# Zotino_BNC_Adapter.net
KiCad netlist of a schematic drawn in Altium Designer
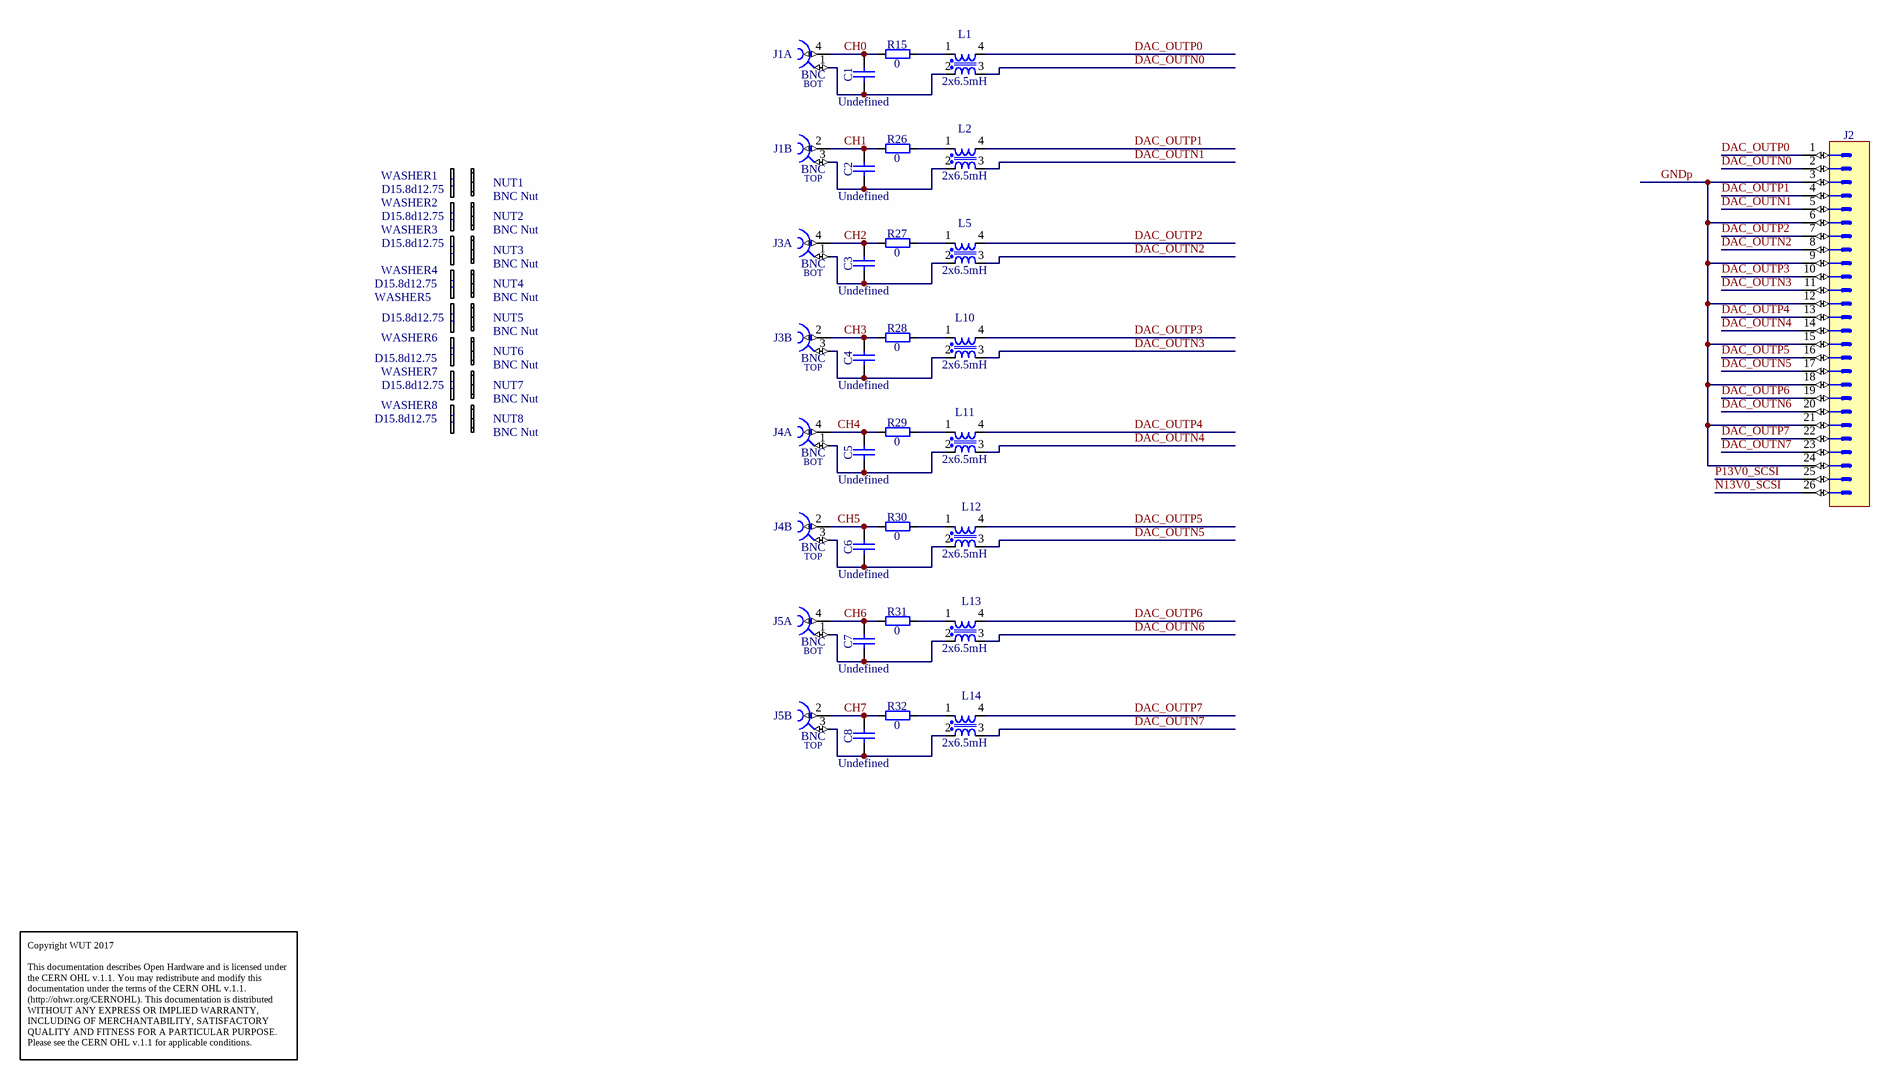
[diagram p0: Zotino_BNC_Adapter.SchDoc]

(export (version "E")
  (design (tool "Eeschema 10.0.6"))
  (components
    (comp (ref "C1")
      (value "Undefined")
      (footprint "CAPC2012X135N")
      (description "Non-polarised capacitor")
      (fields (field (name "PART NUMBER") "CC0805_NO-VALUE") (field (name "AUTHOR") "CERN DEM JLC"))
      (libsource (lib "Capacitors") (part "Capacitor - non polarized"))
    )
    (comp (ref "C2")
      (value "Undefined")
      (footprint "CAPC2012X135N")
      (description "Non-polarised capacitor")
      (fields (field (name "PART NUMBER") "CC0805_NO-VALUE") (field (name "AUTHOR") "CERN DEM JLC"))
      (libsource (lib "Capacitors") (part "Capacitor - non polarized"))
    )
    (comp (ref "C3")
      (value "Undefined")
      (footprint "CAPC2012X135N")
      (description "Non-polarised capacitor")
      (fields (field (name "PART NUMBER") "CC0805_NO-VALUE") (field (name "AUTHOR") "CERN DEM JLC"))
      (libsource (lib "Capacitors") (part "Capacitor - non polarized"))
    )
    (comp (ref "C4")
      (value "Undefined")
      (footprint "CAPC2012X135N")
      (description "Non-polarised capacitor")
      (fields (field (name "PART NUMBER") "CC0805_NO-VALUE") (field (name "AUTHOR") "CERN DEM JLC"))
      (libsource (lib "Capacitors") (part "Capacitor - non polarized"))
    )
    (comp (ref "C5")
      (value "Undefined")
      (footprint "CAPC2012X135N")
      (description "Non-polarised capacitor")
      (fields (field (name "PART NUMBER") "CC0805_NO-VALUE") (field (name "AUTHOR") "CERN DEM JLC"))
      (libsource (lib "Capacitors") (part "Capacitor - non polarized"))
    )
    (comp (ref "C6")
      (value "Undefined")
      (footprint "CAPC2012X135N")
      (description "Non-polarised capacitor")
      (fields (field (name "PART NUMBER") "CC0805_NO-VALUE") (field (name "AUTHOR") "CERN DEM JLC"))
      (libsource (lib "Capacitors") (part "Capacitor - non polarized"))
    )
    (comp (ref "C7")
      (value "Undefined")
      (footprint "CAPC2012X135N")
      (description "Non-polarised capacitor")
      (fields (field (name "PART NUMBER") "CC0805_NO-VALUE") (field (name "AUTHOR") "CERN DEM JLC"))
      (libsource (lib "Capacitors") (part "Capacitor - non polarized"))
    )
    (comp (ref "C8")
      (value "Undefined")
      (footprint "CAPC2012X135N")
      (description "Non-polarised capacitor")
      (fields (field (name "PART NUMBER") "CC0805_NO-VALUE") (field (name "AUTHOR") "CERN DEM JLC"))
      (libsource (lib "Capacitors") (part "Capacitor - non polarized"))
    )
    (comp (ref "J1")
      (value "BNC")
      (footprint "RENHOTEC_RHT-610-0049")
      (description "Dual Right Angle 50 Ohm BNC Jack, White Valox Case")
      (fields
        (field (name "PART NUMBER") "RENHOTEC_RHT-610-0049")
        (field (name "MANUFACTURER") "RENHOTEC")
        (field (name "AUTHOR") "GK")
      )
      (libsource (lib "LIBRARY_SCH") (part "CON_BNC_DUAL"))
    )
    (comp (ref "J2")
      (value "Header 26")
      (footprint "3M_N2526-6003RB")
      (description "Connector 26 Male")
      (fields
        (field (name "PART NUMBER") "3M_N2526-6003RB")
        (field (name "MANUFACTURER") "3M")
        (field (name "AUTHOR") "CERN DEM JLC")
      )
      (libsource (lib "Connectors") (part "Connector 26 Male"))
    )
    (comp (ref "J3")
      (value "BNC")
      (footprint "RENHOTEC_RHT-610-0049")
      (description "Dual Right Angle 50 Ohm BNC Jack, White Valox Case")
      (fields
        (field (name "PART NUMBER") "RENHOTEC_RHT-610-0049")
        (field (name "MANUFACTURER") "RENHOTEC")
        (field (name "AUTHOR") "GK")
      )
      (libsource (lib "LIBRARY_SCH") (part "CON_BNC_DUAL"))
    )
    (comp (ref "J4")
      (value "BNC")
      (footprint "RENHOTEC_RHT-610-0049")
      (description "Dual Right Angle 50 Ohm BNC Jack, White Valox Case")
      (fields
        (field (name "PART NUMBER") "RENHOTEC_RHT-610-0049")
        (field (name "MANUFACTURER") "RENHOTEC")
        (field (name "AUTHOR") "GK")
      )
      (libsource (lib "LIBRARY_SCH") (part "CON_BNC_DUAL"))
    )
    (comp (ref "J5")
      (value "BNC")
      (footprint "RENHOTEC_RHT-610-0049")
      (description "Dual Right Angle 50 Ohm BNC Jack, White Valox Case")
      (fields
        (field (name "PART NUMBER") "RENHOTEC_RHT-610-0049")
        (field (name "MANUFACTURER") "RENHOTEC")
        (field (name "AUTHOR") "GK")
      )
      (libsource (lib "LIBRARY_SCH") (part "CON_BNC_DUAL"))
    )
    (comp (ref "L1")
      (value "2x6.5mH")
      (footprint "IND_WURTH_WE-SL2")
      (description "Inductor Common Mode")
      (fields
        (field (name "PART NUMBER") "IND_6.5MH_50%_WURTH_WE-SL2-744229")
        (field (name "POWER") "400mA")
        (field (name "AUTHOR") "CERN DEM JLC")
      )
      (libsource (lib "Inductors & Transformers") (part "Inductor Common Mode 1Dot-4 2Dot-3"))
    )
    (comp (ref "L2")
      (value "2x6.5mH")
      (footprint "IND_WURTH_WE-SL2")
      (description "Inductor Common Mode")
      (fields
        (field (name "PART NUMBER") "IND_6.5MH_50%_WURTH_WE-SL2-744229")
        (field (name "POWER") "400mA")
        (field (name "AUTHOR") "CERN DEM JLC")
      )
      (libsource (lib "Inductors & Transformers") (part "Inductor Common Mode 1Dot-4 2Dot-3"))
    )
    (comp (ref "L5")
      (value "2x6.5mH")
      (footprint "IND_WURTH_WE-SL2")
      (description "Inductor Common Mode")
      (fields
        (field (name "PART NUMBER") "IND_6.5MH_50%_WURTH_WE-SL2-744229")
        (field (name "POWER") "400mA")
        (field (name "AUTHOR") "CERN DEM JLC")
      )
      (libsource (lib "Inductors & Transformers") (part "Inductor Common Mode 1Dot-4 2Dot-3"))
    )
    (comp (ref "L10")
      (value "2x6.5mH")
      (footprint "IND_WURTH_WE-SL2")
      (description "Inductor Common Mode")
      (fields
        (field (name "PART NUMBER") "IND_6.5MH_50%_WURTH_WE-SL2-744229")
        (field (name "POWER") "400mA")
        (field (name "AUTHOR") "CERN DEM JLC")
      )
      (libsource (lib "Inductors & Transformers") (part "Inductor Common Mode 1Dot-4 2Dot-3"))
    )
    (comp (ref "L11")
      (value "2x6.5mH")
      (footprint "IND_WURTH_WE-SL2")
      (description "Inductor Common Mode")
      (fields
        (field (name "PART NUMBER") "IND_6.5MH_50%_WURTH_WE-SL2-744229")
        (field (name "POWER") "400mA")
        (field (name "AUTHOR") "CERN DEM JLC")
      )
      (libsource (lib "Inductors & Transformers") (part "Inductor Common Mode 1Dot-4 2Dot-3"))
    )
    (comp (ref "L12")
      (value "2x6.5mH")
      (footprint "IND_WURTH_WE-SL2")
      (description "Inductor Common Mode")
      (fields
        (field (name "PART NUMBER") "IND_6.5MH_50%_WURTH_WE-SL2-744229")
        (field (name "POWER") "400mA")
        (field (name "AUTHOR") "CERN DEM JLC")
      )
      (libsource (lib "Inductors & Transformers") (part "Inductor Common Mode 1Dot-4 2Dot-3"))
    )
    (comp (ref "L13")
      (value "2x6.5mH")
      (footprint "IND_WURTH_WE-SL2")
      (description "Inductor Common Mode")
      (fields
        (field (name "PART NUMBER") "IND_6.5MH_50%_WURTH_WE-SL2-744229")
        (field (name "POWER") "400mA")
        (field (name "AUTHOR") "CERN DEM JLC")
      )
      (libsource (lib "Inductors & Transformers") (part "Inductor Common Mode 1Dot-4 2Dot-3"))
    )
    (comp (ref "L14")
      (value "2x6.5mH")
      (footprint "IND_WURTH_WE-SL2")
      (description "Inductor Common Mode")
      (fields
        (field (name "PART NUMBER") "IND_6.5MH_50%_WURTH_WE-SL2-744229")
        (field (name "POWER") "400mA")
        (field (name "AUTHOR") "CERN DEM JLC")
      )
      (libsource (lib "Inductors & Transformers") (part "Inductor Common Mode 1Dot-4 2Dot-3"))
    )
    (comp (ref "NUT1")
      (value "BNC Nut")
      (footprint "TE_1-329631-2")
      (description "BNC nut")
      (fields
        (field (name "PART NUMBER") "TE_1-329631-2")
        (field (name "MANUFACTURER") "TE")
        (field (name "AUTHOR") "CERN DEM JLC")
      )
      (libsource (lib "LIBRARY_SCH") (part "MECH_BNC_NUT"))
    )
    (comp (ref "NUT2")
      (value "BNC Nut")
      (footprint "TE_1-329631-2")
      (description "BNC nut")
      (fields
        (field (name "PART NUMBER") "TE_1-329631-2")
        (field (name "MANUFACTURER") "TE")
        (field (name "AUTHOR") "CERN DEM JLC")
      )
      (libsource (lib "LIBRARY_SCH") (part "MECH_BNC_NUT"))
    )
    (comp (ref "NUT3")
      (value "BNC Nut")
      (footprint "TE_1-329631-2")
      (description "BNC nut")
      (fields
        (field (name "PART NUMBER") "TE_1-329631-2")
        (field (name "MANUFACTURER") "TE")
        (field (name "AUTHOR") "CERN DEM JLC")
      )
      (libsource (lib "LIBRARY_SCH") (part "MECH_BNC_NUT"))
    )
    (comp (ref "NUT4")
      (value "BNC Nut")
      (footprint "TE_1-329631-2")
      (description "BNC nut")
      (fields
        (field (name "PART NUMBER") "TE_1-329631-2")
        (field (name "MANUFACTURER") "TE")
        (field (name "AUTHOR") "CERN DEM JLC")
      )
      (libsource (lib "LIBRARY_SCH") (part "MECH_BNC_NUT"))
    )
    (comp (ref "NUT5")
      (value "BNC Nut")
      (footprint "TE_1-329631-2")
      (description "BNC nut")
      (fields
        (field (name "PART NUMBER") "TE_1-329631-2")
        (field (name "MANUFACTURER") "TE")
        (field (name "AUTHOR") "CERN DEM JLC")
      )
      (libsource (lib "LIBRARY_SCH") (part "MECH_BNC_NUT"))
    )
    (comp (ref "NUT6")
      (value "BNC Nut")
      (footprint "TE_1-329631-2")
      (description "BNC nut")
      (fields
        (field (name "PART NUMBER") "TE_1-329631-2")
        (field (name "MANUFACTURER") "TE")
        (field (name "AUTHOR") "CERN DEM JLC")
      )
      (libsource (lib "LIBRARY_SCH") (part "MECH_BNC_NUT"))
    )
    (comp (ref "NUT7")
      (value "BNC Nut")
      (footprint "TE_1-329631-2")
      (description "BNC nut")
      (fields
        (field (name "PART NUMBER") "TE_1-329631-2")
        (field (name "MANUFACTURER") "TE")
        (field (name "AUTHOR") "CERN DEM JLC")
      )
      (libsource (lib "LIBRARY_SCH") (part "MECH_BNC_NUT"))
    )
    (comp (ref "NUT8")
      (value "BNC Nut")
      (footprint "TE_1-329631-2")
      (description "BNC nut")
      (fields
        (field (name "PART NUMBER") "TE_1-329631-2")
        (field (name "MANUFACTURER") "TE")
        (field (name "AUTHOR") "CERN DEM JLC")
      )
      (libsource (lib "LIBRARY_SCH") (part "MECH_BNC_NUT"))
    )
    (comp (ref "R15")
      (value "0")
      (footprint "RESC1608X55N")
      (description "Resistor")
      (fields
        (field (name "PART NUMBER") "R0603_0R_JUMPER")
        (field (name "MANUFACTURER") "GENERIC")
        (field (name "AUTHOR") "CERN DEM JLC")
      )
      (libsource (lib "Resistors") (part "Resistor"))
    )
    (comp (ref "R26")
      (value "0")
      (footprint "RESC1608X55N")
      (description "Resistor")
      (fields
        (field (name "PART NUMBER") "R0603_0R_JUMPER")
        (field (name "MANUFACTURER") "GENERIC")
        (field (name "AUTHOR") "CERN DEM JLC")
      )
      (libsource (lib "Resistors") (part "Resistor"))
    )
    (comp (ref "R27")
      (value "0")
      (footprint "RESC1608X55N")
      (description "Resistor")
      (fields
        (field (name "PART NUMBER") "R0603_0R_JUMPER")
        (field (name "MANUFACTURER") "GENERIC")
        (field (name "AUTHOR") "CERN DEM JLC")
      )
      (libsource (lib "Resistors") (part "Resistor"))
    )
    (comp (ref "R28")
      (value "0")
      (footprint "RESC1608X55N")
      (description "Resistor")
      (fields
        (field (name "PART NUMBER") "R0603_0R_JUMPER")
        (field (name "MANUFACTURER") "GENERIC")
        (field (name "AUTHOR") "CERN DEM JLC")
      )
      (libsource (lib "Resistors") (part "Resistor"))
    )
    (comp (ref "R29")
      (value "0")
      (footprint "RESC1608X55N")
      (description "Resistor")
      (fields
        (field (name "PART NUMBER") "R0603_0R_JUMPER")
        (field (name "MANUFACTURER") "GENERIC")
        (field (name "AUTHOR") "CERN DEM JLC")
      )
      (libsource (lib "Resistors") (part "Resistor"))
    )
    (comp (ref "R30")
      (value "0")
      (footprint "RESC1608X55N")
      (description "Resistor")
      (fields
        (field (name "PART NUMBER") "R0603_0R_JUMPER")
        (field (name "MANUFACTURER") "GENERIC")
        (field (name "AUTHOR") "CERN DEM JLC")
      )
      (libsource (lib "Resistors") (part "Resistor"))
    )
    (comp (ref "R31")
      (value "0")
      (footprint "RESC1608X55N")
      (description "Resistor")
      (fields
        (field (name "PART NUMBER") "R0603_0R_JUMPER")
        (field (name "MANUFACTURER") "GENERIC")
        (field (name "AUTHOR") "CERN DEM JLC")
      )
      (libsource (lib "Resistors") (part "Resistor"))
    )
    (comp (ref "R32")
      (value "0")
      (footprint "RESC1608X55N")
      (description "Resistor")
      (fields
        (field (name "PART NUMBER") "R0603_0R_JUMPER")
        (field (name "MANUFACTURER") "GENERIC")
        (field (name "AUTHOR") "CERN DEM JLC")
      )
      (libsource (lib "Resistors") (part "Resistor"))
    )
    (comp (ref "WASHER1")
      (value "D15.8d12.75")
      (footprint "TE_1-1634817-0")
      (description "BNC Washer")
      (fields
        (field (name "PART NUMBER") "TE_1-1634817-0")
        (field (name "MANUFACTURER") "TE")
        (field (name "AUTHOR") "GK")
      )
      (libsource (lib "LIBRARY_SCH") (part "MECH_BNC_WASHER"))
    )
    (comp (ref "WASHER2")
      (value "D15.8d12.75")
      (footprint "TE_1-1634817-0")
      (description "BNC Washer")
      (fields
        (field (name "PART NUMBER") "TE_1-1634817-0")
        (field (name "MANUFACTURER") "TE")
        (field (name "AUTHOR") "GK")
      )
      (libsource (lib "LIBRARY_SCH") (part "MECH_BNC_WASHER"))
    )
    (comp (ref "WASHER3")
      (value "D15.8d12.75")
      (footprint "TE_1-1634817-0")
      (description "BNC Washer")
      (fields
        (field (name "PART NUMBER") "TE_1-1634817-0")
        (field (name "MANUFACTURER") "TE")
        (field (name "AUTHOR") "GK")
      )
      (libsource (lib "LIBRARY_SCH") (part "MECH_BNC_WASHER"))
    )
    (comp (ref "WASHER4")
      (value "D15.8d12.75")
      (footprint "TE_1-1634817-0")
      (description "BNC Washer")
      (fields
        (field (name "PART NUMBER") "TE_1-1634817-0")
        (field (name "MANUFACTURER") "TE")
        (field (name "AUTHOR") "GK")
      )
      (libsource (lib "LIBRARY_SCH") (part "MECH_BNC_WASHER"))
    )
    (comp (ref "WASHER5")
      (value "D15.8d12.75")
      (footprint "TE_1-1634817-0")
      (description "BNC Washer")
      (fields
        (field (name "PART NUMBER") "TE_1-1634817-0")
        (field (name "MANUFACTURER") "TE")
        (field (name "AUTHOR") "GK")
      )
      (libsource (lib "LIBRARY_SCH") (part "MECH_BNC_WASHER"))
    )
    (comp (ref "WASHER6")
      (value "D15.8d12.75")
      (footprint "TE_1-1634817-0")
      (description "BNC Washer")
      (fields
        (field (name "PART NUMBER") "TE_1-1634817-0")
        (field (name "MANUFACTURER") "TE")
        (field (name "AUTHOR") "GK")
      )
      (libsource (lib "LIBRARY_SCH") (part "MECH_BNC_WASHER"))
    )
    (comp (ref "WASHER7")
      (value "D15.8d12.75")
      (footprint "TE_1-1634817-0")
      (description "BNC Washer")
      (fields
        (field (name "PART NUMBER") "TE_1-1634817-0")
        (field (name "MANUFACTURER") "TE")
        (field (name "AUTHOR") "GK")
      )
      (libsource (lib "LIBRARY_SCH") (part "MECH_BNC_WASHER"))
    )
    (comp (ref "WASHER8")
      (value "D15.8d12.75")
      (footprint "TE_1-1634817-0")
      (description "BNC Washer")
      (fields
        (field (name "PART NUMBER") "TE_1-1634817-0")
        (field (name "MANUFACTURER") "TE")
        (field (name "AUTHOR") "GK")
      )
      (libsource (lib "LIBRARY_SCH") (part "MECH_BNC_WASHER"))
    )
  )
  (nets
    (net (code "1") (name "/CH0") (class "Default")
      (node (ref "C1") (pin "2") (pinfunction "2_2") (pintype "passive"))
      (node (ref "J1") (pin "4") (pinfunction "4_4") (pintype "bidirectional"))
      (node (ref "R15") (pin "1") (pinfunction "1_1") (pintype "passive"))
    )
    (net (code "2") (name "/CH1") (class "Default")
      (node (ref "C2") (pin "2") (pinfunction "2_2") (pintype "passive"))
      (node (ref "J1") (pin "2") (pinfunction "2_2") (pintype "bidirectional"))
      (node (ref "R26") (pin "1") (pinfunction "1_1") (pintype "passive"))
    )
    (net (code "3") (name "/CH2") (class "Default")
      (node (ref "C3") (pin "2") (pinfunction "2_2") (pintype "passive"))
      (node (ref "J3") (pin "4") (pinfunction "4_4") (pintype "bidirectional"))
      (node (ref "R27") (pin "1") (pinfunction "1_1") (pintype "passive"))
    )
    (net (code "4") (name "/CH3") (class "Default")
      (node (ref "C4") (pin "2") (pinfunction "2_2") (pintype "passive"))
      (node (ref "J3") (pin "2") (pinfunction "2_2") (pintype "bidirectional"))
      (node (ref "R28") (pin "1") (pinfunction "1_1") (pintype "passive"))
    )
    (net (code "5") (name "/CH4") (class "Default")
      (node (ref "C5") (pin "2") (pinfunction "2_2") (pintype "passive"))
      (node (ref "J4") (pin "4") (pinfunction "4_4") (pintype "bidirectional"))
      (node (ref "R29") (pin "1") (pinfunction "1_1") (pintype "passive"))
    )
    (net (code "6") (name "/CH5") (class "Default")
      (node (ref "C6") (pin "2") (pinfunction "2_2") (pintype "passive"))
      (node (ref "J4") (pin "2") (pinfunction "2_2") (pintype "bidirectional"))
      (node (ref "R30") (pin "1") (pinfunction "1_1") (pintype "passive"))
    )
    (net (code "7") (name "/CH6") (class "Default")
      (node (ref "C7") (pin "2") (pinfunction "2_2") (pintype "passive"))
      (node (ref "J5") (pin "4") (pinfunction "4_4") (pintype "bidirectional"))
      (node (ref "R31") (pin "1") (pinfunction "1_1") (pintype "passive"))
    )
    (net (code "8") (name "/CH7") (class "Default")
      (node (ref "C8") (pin "2") (pinfunction "2_2") (pintype "passive"))
      (node (ref "J5") (pin "2") (pinfunction "2_2") (pintype "bidirectional"))
      (node (ref "R32") (pin "1") (pinfunction "1_1") (pintype "passive"))
    )
    (net (code "9") (name "/DAC_OUTN0") (class "Default")
      (node (ref "J2") (pin "2") (pinfunction "2_2") (pintype "bidirectional"))
      (node (ref "L1") (pin "3") (pinfunction "3_3") (pintype "passive"))
    )
    (net (code "10") (name "/DAC_OUTN1") (class "Default")
      (node (ref "J2") (pin "5") (pinfunction "5_5") (pintype "bidirectional"))
      (node (ref "L2") (pin "3") (pinfunction "3_3") (pintype "passive"))
    )
    (net (code "11") (name "/DAC_OUTN2") (class "Default")
      (node (ref "J2") (pin "8") (pinfunction "8_8") (pintype "bidirectional"))
      (node (ref "L5") (pin "3") (pinfunction "3_3") (pintype "passive"))
    )
    (net (code "12") (name "/DAC_OUTN3") (class "Default")
      (node (ref "J2") (pin "11") (pinfunction "11_11") (pintype "bidirectional"))
      (node (ref "L10") (pin "3") (pinfunction "3_3") (pintype "passive"))
    )
    (net (code "13") (name "/DAC_OUTN4") (class "Default")
      (node (ref "J2") (pin "14") (pinfunction "14_14") (pintype "bidirectional"))
      (node (ref "L11") (pin "3") (pinfunction "3_3") (pintype "passive"))
    )
    (net (code "14") (name "/DAC_OUTN5") (class "Default")
      (node (ref "J2") (pin "17") (pinfunction "17_17") (pintype "bidirectional"))
      (node (ref "L12") (pin "3") (pinfunction "3_3") (pintype "passive"))
    )
    (net (code "15") (name "/DAC_OUTN6") (class "Default")
      (node (ref "J2") (pin "20") (pinfunction "20_20") (pintype "bidirectional"))
      (node (ref "L13") (pin "3") (pinfunction "3_3") (pintype "passive"))
    )
    (net (code "16") (name "/DAC_OUTN7") (class "Default")
      (node (ref "J2") (pin "23") (pinfunction "23_23") (pintype "bidirectional"))
      (node (ref "L14") (pin "3") (pinfunction "3_3") (pintype "passive"))
    )
    (net (code "17") (name "/DAC_OUTP0") (class "Default")
      (node (ref "J2") (pin "1") (pinfunction "1_1") (pintype "bidirectional"))
      (node (ref "L1") (pin "4") (pinfunction "4_4") (pintype "passive"))
    )
    (net (code "18") (name "/DAC_OUTP1") (class "Default")
      (node (ref "J2") (pin "4") (pinfunction "4_4") (pintype "bidirectional"))
      (node (ref "L2") (pin "4") (pinfunction "4_4") (pintype "passive"))
    )
    (net (code "19") (name "/DAC_OUTP2") (class "Default")
      (node (ref "J2") (pin "7") (pinfunction "7_7") (pintype "bidirectional"))
      (node (ref "L5") (pin "4") (pinfunction "4_4") (pintype "passive"))
    )
    (net (code "20") (name "/DAC_OUTP3") (class "Default")
      (node (ref "J2") (pin "10") (pinfunction "10_10") (pintype "bidirectional"))
      (node (ref "L10") (pin "4") (pinfunction "4_4") (pintype "passive"))
    )
    (net (code "21") (name "/DAC_OUTP4") (class "Default")
      (node (ref "J2") (pin "13") (pinfunction "13_13") (pintype "bidirectional"))
      (node (ref "L11") (pin "4") (pinfunction "4_4") (pintype "passive"))
    )
    (net (code "22") (name "/DAC_OUTP5") (class "Default")
      (node (ref "J2") (pin "16") (pinfunction "16_16") (pintype "bidirectional"))
      (node (ref "L12") (pin "4") (pinfunction "4_4") (pintype "passive"))
    )
    (net (code "23") (name "/DAC_OUTP6") (class "Default")
      (node (ref "J2") (pin "19") (pinfunction "19_19") (pintype "bidirectional"))
      (node (ref "L13") (pin "4") (pinfunction "4_4") (pintype "passive"))
    )
    (net (code "24") (name "/DAC_OUTP7") (class "Default")
      (node (ref "J2") (pin "22") (pinfunction "22_22") (pintype "bidirectional"))
      (node (ref "L14") (pin "4") (pinfunction "4_4") (pintype "passive"))
    )
    (net (code "25") (name "/GNDp") (class "Default")
      (node (ref "J2") (pin "12") (pinfunction "12_12") (pintype "bidirectional"))
      (node (ref "J2") (pin "15") (pinfunction "15_15") (pintype "bidirectional"))
      (node (ref "J2") (pin "18") (pinfunction "18_18") (pintype "bidirectional"))
      (node (ref "J2") (pin "21") (pinfunction "21_21") (pintype "bidirectional"))
      (node (ref "J2") (pin "24") (pinfunction "24_24") (pintype "bidirectional"))
      (node (ref "J2") (pin "3") (pinfunction "3_3") (pintype "bidirectional"))
      (node (ref "J2") (pin "6") (pinfunction "6_6") (pintype "bidirectional"))
      (node (ref "J2") (pin "9") (pinfunction "9_9") (pintype "bidirectional"))
    )
    (net (code "26") (name "/N13V0_SCSI") (class "Default")
      (node (ref "J2") (pin "26") (pinfunction "26_26") (pintype "bidirectional"))
    )
    (net (code "27") (name "/P13V0_SCSI") (class "Default")
      (node (ref "J2") (pin "25") (pinfunction "25_25") (pintype "bidirectional"))
    )
    (net (code "28") (name "Net-(C1-Pad1)") (class "Default")
      (node (ref "C1") (pin "1") (pinfunction "1_1") (pintype "passive"))
      (node (ref "J1") (pin "1") (pinfunction "1_1") (pintype "bidirectional"))
      (node (ref "L1") (pin "2") (pinfunction "2_2") (pintype "passive"))
    )
    (net (code "29") (name "Net-(C2-Pad1)") (class "Default")
      (node (ref "C2") (pin "1") (pinfunction "1_1") (pintype "passive"))
      (node (ref "J1") (pin "3") (pinfunction "3_3") (pintype "bidirectional"))
      (node (ref "L2") (pin "2") (pinfunction "2_2") (pintype "passive"))
    )
    (net (code "30") (name "Net-(C3-Pad1)") (class "Default")
      (node (ref "C3") (pin "1") (pinfunction "1_1") (pintype "passive"))
      (node (ref "J3") (pin "1") (pinfunction "1_1") (pintype "bidirectional"))
      (node (ref "L5") (pin "2") (pinfunction "2_2") (pintype "passive"))
    )
    (net (code "31") (name "Net-(C4-Pad1)") (class "Default")
      (node (ref "C4") (pin "1") (pinfunction "1_1") (pintype "passive"))
      (node (ref "J3") (pin "3") (pinfunction "3_3") (pintype "bidirectional"))
      (node (ref "L10") (pin "2") (pinfunction "2_2") (pintype "passive"))
    )
    (net (code "32") (name "Net-(C5-Pad1)") (class "Default")
      (node (ref "C5") (pin "1") (pinfunction "1_1") (pintype "passive"))
      (node (ref "J4") (pin "1") (pinfunction "1_1") (pintype "bidirectional"))
      (node (ref "L11") (pin "2") (pinfunction "2_2") (pintype "passive"))
    )
    (net (code "33") (name "Net-(C6-Pad1)") (class "Default")
      (node (ref "C6") (pin "1") (pinfunction "1_1") (pintype "passive"))
      (node (ref "J4") (pin "3") (pinfunction "3_3") (pintype "bidirectional"))
      (node (ref "L12") (pin "2") (pinfunction "2_2") (pintype "passive"))
    )
    (net (code "34") (name "Net-(C7-Pad1)") (class "Default")
      (node (ref "C7") (pin "1") (pinfunction "1_1") (pintype "passive"))
      (node (ref "J5") (pin "1") (pinfunction "1_1") (pintype "bidirectional"))
      (node (ref "L13") (pin "2") (pinfunction "2_2") (pintype "passive"))
    )
    (net (code "35") (name "Net-(C8-Pad1)") (class "Default")
      (node (ref "C8") (pin "1") (pinfunction "1_1") (pintype "passive"))
      (node (ref "J5") (pin "3") (pinfunction "3_3") (pintype "bidirectional"))
      (node (ref "L14") (pin "2") (pinfunction "2_2") (pintype "passive"))
    )
    (net (code "36") (name "Net-(L1-Pad1)") (class "Default")
      (node (ref "L1") (pin "1") (pinfunction "1_1") (pintype "passive"))
      (node (ref "R15") (pin "2") (pinfunction "2_2") (pintype "passive"))
    )
    (net (code "37") (name "Net-(L2-Pad1)") (class "Default")
      (node (ref "L2") (pin "1") (pinfunction "1_1") (pintype "passive"))
      (node (ref "R26") (pin "2") (pinfunction "2_2") (pintype "passive"))
    )
    (net (code "38") (name "Net-(L5-Pad1)") (class "Default")
      (node (ref "L5") (pin "1") (pinfunction "1_1") (pintype "passive"))
      (node (ref "R27") (pin "2") (pinfunction "2_2") (pintype "passive"))
    )
    (net (code "39") (name "Net-(L10-Pad1)") (class "Default")
      (node (ref "L10") (pin "1") (pinfunction "1_1") (pintype "passive"))
      (node (ref "R28") (pin "2") (pinfunction "2_2") (pintype "passive"))
    )
    (net (code "40") (name "Net-(L11-Pad1)") (class "Default")
      (node (ref "L11") (pin "1") (pinfunction "1_1") (pintype "passive"))
      (node (ref "R29") (pin "2") (pinfunction "2_2") (pintype "passive"))
    )
    (net (code "41") (name "Net-(L12-Pad1)") (class "Default")
      (node (ref "L12") (pin "1") (pinfunction "1_1") (pintype "passive"))
      (node (ref "R30") (pin "2") (pinfunction "2_2") (pintype "passive"))
    )
    (net (code "42") (name "Net-(L13-Pad1)") (class "Default")
      (node (ref "L13") (pin "1") (pinfunction "1_1") (pintype "passive"))
      (node (ref "R31") (pin "2") (pinfunction "2_2") (pintype "passive"))
    )
    (net (code "43") (name "Net-(L14-Pad1)") (class "Default")
      (node (ref "L14") (pin "1") (pinfunction "1_1") (pintype "passive"))
      (node (ref "R32") (pin "2") (pinfunction "2_2") (pintype "passive"))
    )
  )
)
